# DC-DC_3V3.net
KiCad netlist of a schematic drawn in Altium Designer
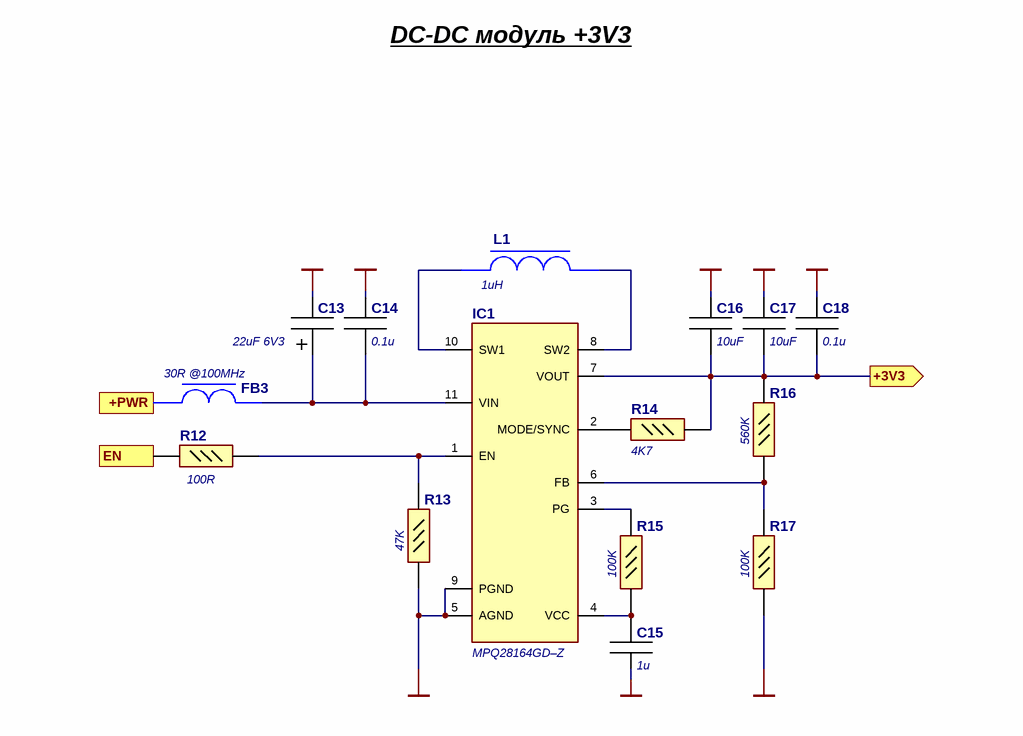
[diagram p0: DC-DC модуль +3V3.SchDoc]

(export (version "E")
  (design (tool "Eeschema 10.0.6"))
  (components
    (comp (ref "C13")
      (value "22uF 6V3")
      (footprint ":CAP1206 C3216-18")
      (description "22uF Molded Tantalum Capacitors 6.3V 1206 (3216 Metric) 300mOhm @ 100kHz")
      (fields (field (name "MANUFACTURER_PART_NUMBER") "TPSA226K006R0300"))
      (libsource (lib "Capacitors 1206") (part "TPSA226K006R0300"))
    )
    (comp (ref "C14")
      (value "0.1u")
      (footprint ":CAP0402 100x50x50")
      (description "±10% 25V Ceramic Capacitor X7R 0402 (1005 Metric)")
      (fields
        (field (name "MANUFACTURER_PART_NUMBER") "GRM155R71E104KE14J")
        (field (name "MOUSER PART NUMBER") "81-GRM155R71E104KE4J")
      )
      (libsource (lib "Capacitors 0402") (part "GRM155R71E104KE14J"))
    )
    (comp (ref "C15")
      (value "1u")
      (footprint ":CAP0603 C1608х08")
      (description "±10% 25V Ceramic Capacitor X7R 0603 (1608 Metric)")
      (fields (field (name "MANUFACTURER_PART_NUMBER") "GCM188R71E105KA64D"))
      (libsource (lib "Capacitors 0603") (part "GCM188R71E105KA64D"))
    )
    (comp (ref "C16")
      (value "10uF")
      (footprint ":CAP0805 C2012X125")
      (description "CAP CER 10uF 16V X5R 0805")
      (fields
        (field (name "MANUFACTURER_PART_NUMBER") "C2012X5R1C106M085AC")
        (field (name "MOUSER PART NUMBER") "810-C2012X5R1C106M-2")
      )
      (libsource (lib "Capacitors 0805") (part "C2012X5R1C106M085AC"))
    )
    (comp (ref "C17")
      (value "10uF")
      (footprint ":CAP0805 C2012X125")
      (description "CAP CER 10uF 16V X5R 0805")
      (fields
        (field (name "MANUFACTURER_PART_NUMBER") "C2012X5R1C106M085AC")
        (field (name "MOUSER PART NUMBER") "810-C2012X5R1C106M-2")
      )
      (libsource (lib "Capacitors 0805") (part "C2012X5R1C106M085AC"))
    )
    (comp (ref "C18")
      (value "0.1u")
      (footprint ":CAP0402 100x50x50")
      (description "±10% 25V Ceramic Capacitor X7R 0402 (1005 Metric)")
      (fields
        (field (name "MANUFACTURER_PART_NUMBER") "GRM155R71E104KE14J")
        (field (name "MOUSER PART NUMBER") "81-GRM155R71E104KE4J")
      )
      (libsource (lib "Capacitors 0402") (part "GRM155R71E104KE14J"))
    )
    (comp (ref "FB3")
      (value "30R @100MHz")
      (footprint ":FER BLM18SP300SN1D")
      (description "30 Ohms @ 100MHz 1 Power Line Ferrite Bead 0603 (1608 Metric) 6A 8mOhm")
      (fields
        (field (name "MANUFACTURER_PART_NUMBER") "BLM18SP300SN1D")
        (field (name "MOUSER PART NUMBER") "81-BLM18SP300SN1D")
      )
      (libsource (lib "Ferrite Bead") (part "BLM18SP300SN1D"))
    )
    (comp (ref "IC1")
      (value "MPQ28164GD–Z")
      (footprint ":QFN11 P300X200X100-11N")
      (description "DC/DC Converter \r\n1.2V to 5.5V Input\r\n1.5V to 5V Output 2A")
      (libsource (lib "DC-DC convertors") (part "MPQ28164GD–Z"))
    )
    (comp (ref "L1")
      (value "1uH")
      (footprint ":IND1210 C3225")
      (fields (field (name "MANUFACTURER_PART_NUMBER") "74479299210"))
      (libsource (lib "Inductance") (part "74479299210"))
    )
    (comp (ref "R12")
      (value "RC0402FR-07")
      (footprint ":RES0402")
      (fields (field (name "MANUFACTURER_PART_NUMBER (PART 2: VALUE)") "100R"))
      (libsource (lib "") (part "RC0402FR-07_1"))
    )
    (comp (ref "R13")
      (value "RC0402FR-07")
      (footprint ":RES0402")
      (fields (field (name "MANUFACTURER_PART_NUMBER (PART 2: VALUE)") "47K"))
      (libsource (lib "Resistors 0402") (part "RC0402FR-07"))
    )
    (comp (ref "R14")
      (value "RC0402FR-07")
      (footprint ":RES0402")
      (fields (field (name "MANUFACTURER_PART_NUMBER (PART 2: VALUE)") "4K7"))
      (libsource (lib "") (part "RC0402FR-07_1"))
    )
    (comp (ref "R15")
      (value "RC0402FR-07")
      (footprint ":RES0402")
      (fields (field (name "MANUFACTURER_PART_NUMBER (PART 2: VALUE)") "100K"))
      (libsource (lib "Resistors 0402") (part "RC0402FR-07"))
    )
    (comp (ref "R16")
      (value "RC0402FR-07")
      (footprint ":RES0402")
      (fields (field (name "MANUFACTURER_PART_NUMBER (PART 2: VALUE)") "560K"))
      (libsource (lib "Resistors 0402") (part "RC0402FR-07"))
    )
    (comp (ref "R17")
      (value "RC0402FR-07")
      (footprint ":RES0402")
      (fields (field (name "MANUFACTURER_PART_NUMBER (PART 2: VALUE)") "100K"))
      (libsource (lib "Resistors 0402") (part "RC0402FR-07"))
    )
  )
  (nets
    (net (code "1") (name "/+3V3") (class "Default")
      (node (ref "C16") (pin "1") (pinfunction "1_1") (pintype "passive"))
      (node (ref "C17") (pin "1") (pinfunction "1_1") (pintype "passive"))
      (node (ref "C18") (pin "2") (pinfunction "2_2") (pintype "passive"))
      (node (ref "IC1") (pin "7") (pinfunction "VOUT_7") (pintype "passive"))
      (node (ref "R14") (pin "2") (pinfunction "2_2") (pintype "passive"))
      (node (ref "R16") (pin "2") (pinfunction "2_2") (pintype "passive"))
    )
    (net (code "2") (name "/+PWR") (class "Default")
      (node (ref "FB3") (pin "1") (pinfunction "1_1") (pintype "passive"))
    )
    (net (code "3") (name "/EN") (class "Default")
      (node (ref "R12") (pin "1") (pinfunction "1_1") (pintype "passive"))
    )
    (net (code "4") (name "GND") (class "Default")
      (node (ref "C13") (pin "2") (pinfunction "2_2") (pintype "passive"))
      (node (ref "C14") (pin "1") (pinfunction "1_1") (pintype "passive"))
      (node (ref "C15") (pin "1") (pinfunction "1_1") (pintype "passive"))
      (node (ref "C16") (pin "2") (pinfunction "2_2") (pintype "passive"))
      (node (ref "C17") (pin "2") (pinfunction "2_2") (pintype "passive"))
      (node (ref "C18") (pin "1") (pinfunction "1_1") (pintype "passive"))
      (node (ref "IC1") (pin "5") (pinfunction "AGND_5") (pintype "passive"))
      (node (ref "IC1") (pin "9") (pinfunction "PGND_9") (pintype "passive"))
      (node (ref "R13") (pin "1") (pinfunction "1_1") (pintype "passive"))
      (node (ref "R17") (pin "1") (pinfunction "1_1") (pintype "passive"))
    )
    (net (code "5") (name "Net-(C13-+)") (class "Default")
      (node (ref "C13") (pin "1") (pinfunction "+_1") (pintype "passive"))
      (node (ref "C14") (pin "2") (pinfunction "2_2") (pintype "passive"))
      (node (ref "FB3") (pin "2") (pinfunction "2_2") (pintype "passive"))
      (node (ref "IC1") (pin "11") (pinfunction "VIN_11") (pintype "passive"))
    )
    (net (code "6") (name "Net-(IC1-EN)") (class "Default")
      (node (ref "IC1") (pin "1") (pinfunction "EN_1") (pintype "passive"))
      (node (ref "R12") (pin "2") (pinfunction "2_2") (pintype "passive"))
      (node (ref "R13") (pin "2") (pinfunction "2_2") (pintype "passive"))
    )
    (net (code "7") (name "Net-(IC1-FB)") (class "Default")
      (node (ref "IC1") (pin "6") (pinfunction "FB_6") (pintype "passive"))
      (node (ref "R16") (pin "1") (pinfunction "1_1") (pintype "passive"))
      (node (ref "R17") (pin "2") (pinfunction "2_2") (pintype "passive"))
    )
    (net (code "8") (name "Net-(IC1-MODE{slash}SYNC)") (class "Default")
      (node (ref "IC1") (pin "2") (pinfunction "MODE/SYNC_2") (pintype "passive"))
      (node (ref "R14") (pin "1") (pinfunction "1_1") (pintype "passive"))
    )
    (net (code "9") (name "Net-(IC1-PG)") (class "Default")
      (node (ref "IC1") (pin "3") (pinfunction "PG_3") (pintype "passive"))
      (node (ref "R15") (pin "2") (pinfunction "2_2") (pintype "passive"))
    )
    (net (code "10") (name "Net-(IC1-SW1)") (class "Default")
      (node (ref "IC1") (pin "10") (pinfunction "SW1_10") (pintype "passive"))
      (node (ref "L1") (pin "1") (pinfunction "1_1") (pintype "passive"))
    )
    (net (code "11") (name "Net-(IC1-SW2)") (class "Default")
      (node (ref "IC1") (pin "8") (pinfunction "SW2_8") (pintype "passive"))
      (node (ref "L1") (pin "2") (pinfunction "2_2") (pintype "passive"))
    )
    (net (code "12") (name "Net-(IC1-VCC)") (class "Default")
      (node (ref "C15") (pin "2") (pinfunction "2_2") (pintype "passive"))
      (node (ref "IC1") (pin "4") (pinfunction "VCC_4") (pintype "passive"))
      (node (ref "R15") (pin "1") (pinfunction "1_1") (pintype "passive"))
    )
  )
)
